# untitled.net
KiCad netlist of a schematic drawn in EAGLE
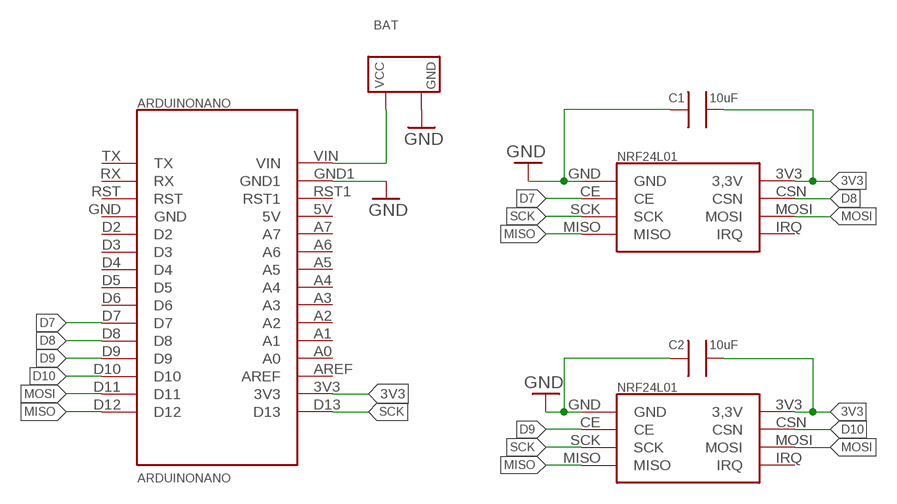
[diagram p0: schematic, sheet 1]

(export (version "E")
  (design (tool "Eeschema 10.0.6"))
  (components
    (comp (ref "ARDUINONANO")
      (value "ARDUINONANO")
      (footprint "eagle-import:ARDUINONANO")
      (libsource (lib "eagle-import") (part "ARDUINONANO"))
    )
    (comp (ref "BAT1")
      (value "BATBAT")
      (footprint "eagle-import:BAT")
      (libsource (lib "eagle-import") (part "BATBAT"))
    )
    (comp (ref "C1")
      (value "NRF24L01")
      (footprint "eagle-import:NRF24L01")
      (libsource (lib "eagle-import") (part "NRF24L01"))
    )
    (comp (ref "C2")
      (value "NRF24L01")
      (footprint "eagle-import:NRF24L01")
      (libsource (lib "eagle-import") (part "NRF24L01"))
    )
    (comp (ref "U$3") (value "C") (footprint "eagle-import:C") (libsource (lib "eagle-import") (part "C")))
    (comp (ref "U$4") (value "C") (footprint "eagle-import:C") (libsource (lib "eagle-import") (part "C")))
  )
  (nets
    (net (code "1") (name "3V3") (class "Default")
      (node (ref "ARDUINONANO") (pin "3V3") (pinfunction "3V3_3V3") (pintype "bidirectional"))
      (node (ref "C1") (pin "3V3") (pinfunction "3,3V_3V3") (pintype "bidirectional"))
      (node (ref "C2") (pin "3V3") (pinfunction "3,3V_3V3") (pintype "bidirectional"))
      (node (ref "U$3") (pin "+") (pinfunction "+_+") (pintype "bidirectional"))
      (node (ref "U$4") (pin "+") (pinfunction "+_+") (pintype "bidirectional"))
    )
    (net (code "2") (name "D7") (class "Default")
      (node (ref "ARDUINONANO") (pin "D7") (pinfunction "D7_D7") (pintype "bidirectional"))
      (node (ref "C2") (pin "CE") (pinfunction "CE_CE") (pintype "bidirectional"))
    )
    (net (code "3") (name "D8") (class "Default")
      (node (ref "ARDUINONANO") (pin "D8") (pinfunction "D8_D8") (pintype "bidirectional"))
      (node (ref "C2") (pin "CSN") (pinfunction "CSN_CSN") (pintype "bidirectional"))
    )
    (net (code "4") (name "D9") (class "Default")
      (node (ref "ARDUINONANO") (pin "D9") (pinfunction "D9_D9") (pintype "bidirectional"))
      (node (ref "C1") (pin "CE") (pinfunction "CE_CE") (pintype "bidirectional"))
    )
    (net (code "5") (name "D10") (class "Default")
      (node (ref "ARDUINONANO") (pin "D10") (pinfunction "D10_D10") (pintype "bidirectional"))
      (node (ref "C1") (pin "CSN") (pinfunction "CSN_CSN") (pintype "bidirectional"))
    )
    (net (code "6") (name "GND") (class "Default")
      (node (ref "ARDUINONANO") (pin "GND1") (pinfunction "GND1_GND1") (pintype "bidirectional"))
      (node (ref "BAT1") (pin "GND") (pinfunction "GND_GND") (pintype "bidirectional"))
      (node (ref "C1") (pin "GND") (pinfunction "GND_GND") (pintype "bidirectional"))
      (node (ref "C2") (pin "GND") (pinfunction "GND_GND") (pintype "bidirectional"))
      (node (ref "U$3") (pin "-") (pinfunction "-_-") (pintype "bidirectional"))
      (node (ref "U$4") (pin "-") (pinfunction "-_-") (pintype "bidirectional"))
    )
    (net (code "7") (name "MISO") (class "Default")
      (node (ref "ARDUINONANO") (pin "D12") (pinfunction "D12_D12") (pintype "bidirectional"))
      (node (ref "C1") (pin "MISO") (pinfunction "MISO_MISO") (pintype "bidirectional"))
      (node (ref "C2") (pin "MISO") (pinfunction "MISO_MISO") (pintype "bidirectional"))
    )
    (net (code "8") (name "MOSI") (class "Default")
      (node (ref "ARDUINONANO") (pin "D11") (pinfunction "D11_D11") (pintype "bidirectional"))
      (node (ref "C1") (pin "MOSI") (pinfunction "MOSI_MOSI") (pintype "bidirectional"))
      (node (ref "C2") (pin "MOSI") (pinfunction "MOSI_MOSI") (pintype "bidirectional"))
    )
    (net (code "9") (name "Net-(ARDUINONANO-PadVIN)") (class "Default")
      (node (ref "ARDUINONANO") (pin "VIN") (pinfunction "VIN_VIN") (pintype "bidirectional"))
      (node (ref "BAT1") (pin "VCC") (pinfunction "VCC_VCC") (pintype "bidirectional"))
    )
    (net (code "10") (name "SCK") (class "Default")
      (node (ref "ARDUINONANO") (pin "D13") (pinfunction "D13_D13") (pintype "bidirectional"))
      (node (ref "C1") (pin "SCK") (pinfunction "SCK_SCK") (pintype "bidirectional"))
      (node (ref "C2") (pin "SCK") (pinfunction "SCK_SCK") (pintype "bidirectional"))
    )
    (net (code "11") (name "unconnected-(ARDUINONANO-Pad5V)") (class "Default")
      (node (ref "ARDUINONANO") (pin "5V") (pinfunction "5V_5V") (pintype "bidirectional"))
    )
    (net (code "12") (name "unconnected-(ARDUINONANO-PadA0)") (class "Default")
      (node (ref "ARDUINONANO") (pin "A0") (pinfunction "A0_A0") (pintype "bidirectional"))
    )
    (net (code "13") (name "unconnected-(ARDUINONANO-PadA1)") (class "Default")
      (node (ref "ARDUINONANO") (pin "A1") (pinfunction "A1_A1") (pintype "bidirectional"))
    )
    (net (code "14") (name "unconnected-(ARDUINONANO-PadA2)") (class "Default")
      (node (ref "ARDUINONANO") (pin "A2") (pinfunction "A2_A2") (pintype "bidirectional"))
    )
    (net (code "15") (name "unconnected-(ARDUINONANO-PadA3)") (class "Default")
      (node (ref "ARDUINONANO") (pin "A3") (pinfunction "A3_A3") (pintype "bidirectional"))
    )
    (net (code "16") (name "unconnected-(ARDUINONANO-PadA4)") (class "Default")
      (node (ref "ARDUINONANO") (pin "A4") (pinfunction "A4_A4") (pintype "bidirectional"))
    )
    (net (code "17") (name "unconnected-(ARDUINONANO-PadA5)") (class "Default")
      (node (ref "ARDUINONANO") (pin "A5") (pinfunction "A5_A5") (pintype "bidirectional"))
    )
    (net (code "18") (name "unconnected-(ARDUINONANO-PadA6)") (class "Default")
      (node (ref "ARDUINONANO") (pin "A6") (pinfunction "A6_A6") (pintype "bidirectional"))
    )
    (net (code "19") (name "unconnected-(ARDUINONANO-PadA7)") (class "Default")
      (node (ref "ARDUINONANO") (pin "A7") (pinfunction "A7_A7") (pintype "bidirectional"))
    )
    (net (code "20") (name "unconnected-(ARDUINONANO-PadAREF)") (class "Default")
      (node (ref "ARDUINONANO") (pin "AREF") (pinfunction "AREF_AREF") (pintype "bidirectional"))
    )
    (net (code "21") (name "unconnected-(ARDUINONANO-PadD2)") (class "Default")
      (node (ref "ARDUINONANO") (pin "D2") (pinfunction "D2_D2") (pintype "bidirectional"))
    )
    (net (code "22") (name "unconnected-(ARDUINONANO-PadD3)") (class "Default")
      (node (ref "ARDUINONANO") (pin "D3") (pinfunction "D3_D3") (pintype "bidirectional"))
    )
    (net (code "23") (name "unconnected-(ARDUINONANO-PadD4)") (class "Default")
      (node (ref "ARDUINONANO") (pin "D4") (pinfunction "D4_D4") (pintype "bidirectional"))
    )
    (net (code "24") (name "unconnected-(ARDUINONANO-PadD5)") (class "Default")
      (node (ref "ARDUINONANO") (pin "D5") (pinfunction "D5_D5") (pintype "bidirectional"))
    )
    (net (code "25") (name "unconnected-(ARDUINONANO-PadD6)") (class "Default")
      (node (ref "ARDUINONANO") (pin "D6") (pinfunction "D6_D6") (pintype "bidirectional"))
    )
    (net (code "26") (name "unconnected-(ARDUINONANO-PadGND)") (class "Default")
      (node (ref "ARDUINONANO") (pin "GND") (pinfunction "GND_GND") (pintype "bidirectional"))
    )
    (net (code "27") (name "unconnected-(ARDUINONANO-PadRST)") (class "Default")
      (node (ref "ARDUINONANO") (pin "RST") (pinfunction "RST_RST") (pintype "bidirectional"))
    )
    (net (code "28") (name "unconnected-(ARDUINONANO-PadRST1)") (class "Default")
      (node (ref "ARDUINONANO") (pin "RST1") (pinfunction "RST1_RST1") (pintype "bidirectional"))
    )
    (net (code "29") (name "unconnected-(ARDUINONANO-PadRX)") (class "Default")
      (node (ref "ARDUINONANO") (pin "RX") (pinfunction "RX_RX") (pintype "bidirectional"))
    )
    (net (code "30") (name "unconnected-(ARDUINONANO-PadTX)") (class "Default")
      (node (ref "ARDUINONANO") (pin "TX") (pinfunction "TX_TX") (pintype "bidirectional"))
    )
    (net (code "31") (name "unconnected-(C1-PadIRQ)") (class "Default")
      (node (ref "C1") (pin "IRQ") (pinfunction "IRQ_IRQ") (pintype "bidirectional"))
    )
    (net (code "32") (name "unconnected-(C2-PadIRQ)") (class "Default")
      (node (ref "C2") (pin "IRQ") (pinfunction "IRQ_IRQ") (pintype "bidirectional"))
    )
  )
)
